# MCU_FM.net
KiCad netlist of a schematic drawn in Altium Designer
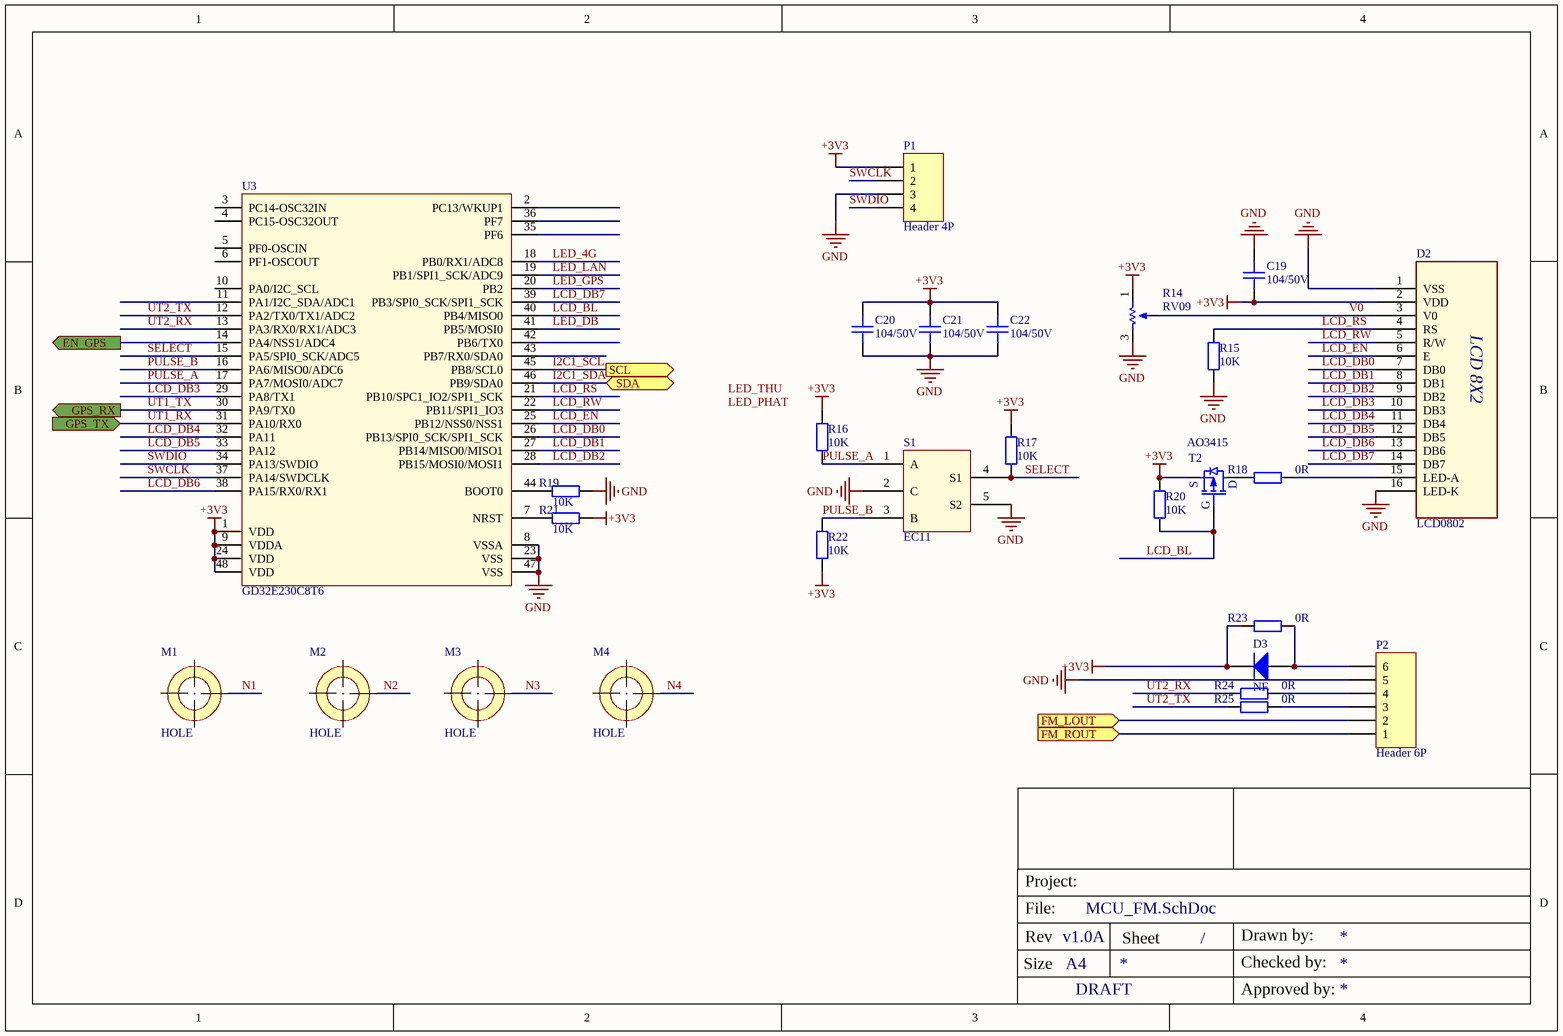
[diagram p0: MCU_FM.SchDoc]

(export (version "E")
  (design (tool "Eeschema 10.0.6"))
  (components
    (comp (ref "C19")
      (value "104/50V")
      (footprint "CAPC-0603 (1608) - HD")
      (description "CAP CER 0.1uF 50V 10% X7R 0603")
      (fields (field (name "MPN") "C0603C104K5RACTU"))
      (libsource (lib "01.Passives") (part "C0603C104K5RACTU"))
    )
    (comp (ref "C20")
      (value "104/50V")
      (footprint "CAPC-0603 (1608) - HD")
      (description "CAP CER 0.1uF 50V 10% X7R 0603")
      (fields (field (name "MPN") "C0603C104K5RACTU"))
      (libsource (lib "01.Passives") (part "C0603C104K5RACTU"))
    )
    (comp (ref "C21")
      (value "104/50V")
      (footprint "CAPC-0603 (1608) - HD")
      (description "CAP CER 0.1uF 50V 10% X7R 0603")
      (fields (field (name "MPN") "C0603C104K5RACTU"))
      (libsource (lib "01.Passives") (part "C0603C104K5RACTU"))
    )
    (comp (ref "C22")
      (value "104/50V")
      (footprint "CAPC-0603 (1608) - HD")
      (description "CAP CER 0.1uF 50V 10% X7R 0603")
      (fields (field (name "MPN") "C0603C104K5RACTU"))
      (libsource (lib "01.Passives") (part "C0603C104K5RACTU"))
    )
    (comp (ref "D2")
      (value "LCD0802")
      (footprint "LCD 8X2 FORM 3")
      (fields (field (name "MFR") "China"))
      (libsource (lib "08.Miscellaneous") (part "LCD0802"))
    )
    (comp (ref "D3")
      (value "NF")
      (footprint "SOD-123")
      (description "Diode Standard 100V 300mA (DC) Surface Mount SOD-123")
      (fields (field (name "PART NUMBER") "1N4148W-7-F"))
      (libsource (lib "Library_Chip") (part "Diode 1N4148"))
    )
    (comp (ref "M1")
      (value "HOLE")
      (footprint "HOLE_3MM_6MM")
      (description "3mm/5mm")
      (fields (field (name "MPN") "None"))
      (libsource (lib "08.Miscellaneous") (part "HOLE_3_5"))
    )
    (comp (ref "M2")
      (value "HOLE")
      (footprint "HOLE_3MM_6MM")
      (description "3mm/5mm")
      (fields (field (name "MPN") "None"))
      (libsource (lib "08.Miscellaneous") (part "HOLE_3_5"))
    )
    (comp (ref "M3")
      (value "HOLE")
      (footprint "HOLE_3MM_6MM")
      (description "3mm/5mm")
      (fields (field (name "MPN") "None"))
      (libsource (lib "08.Miscellaneous") (part "HOLE_3_5"))
    )
    (comp (ref "M4")
      (value "HOLE")
      (footprint "HOLE_3MM_6MM")
      (description "3mm/5mm")
      (fields (field (name "MPN") "None"))
      (libsource (lib "08.Miscellaneous") (part "HOLE_3_5"))
    )
    (comp (ref "P1")
      (value "Header 4P")
      (footprint "HDR1X4 - W")
      (description "Header, 4 Pin Pitch 2.54mm")
      (fields (field (name "MPN") "S1012EC-40-ND"))
      (libsource (lib "04.Header-Connecter") (part "Header 4x1"))
    )
    (comp (ref "P2")
      (value "Header 6P")
      (footprint "HDR1X6 - W")
      (description "Header, 6 Pin Pitch 2.54mm")
      (fields (field (name "MPN") "S1012EC-40-ND"))
      (libsource (lib "04.Header-Connecter") (part "Header 6x1"))
    )
    (comp (ref "R14")
      (value "RV09")
      (footprint "RES_VAR_Type1")
      (description "Variable Resistor 10K")
      (libsource (lib "01.Passives") (part "Res Var RV09"))
    )
    (comp (ref "R15")
      (value "10K")
      (footprint "RESC-0603 (1608) - HD")
      (description "RES SMD 10K OHM 1% 1/10W 0603")
      (fields (field (name "MPN") "RC0603FR-0710KL"))
      (libsource (lib "01.Passives") (part "RC0603FR-0710KL"))
    )
    (comp (ref "R16")
      (value "10K")
      (footprint "RESC-0603 (1608) - HD")
      (description "RES SMD 10K OHM 1% 1/10W 0603")
      (fields (field (name "MPN") "RC0603FR-0710KL"))
      (libsource (lib "01.Passives") (part "RC0603FR-0710KL"))
    )
    (comp (ref "R17")
      (value "10K")
      (footprint "RESC-0603 (1608) - HD")
      (description "RES SMD 10K OHM 1% 1/10W 0603")
      (fields (field (name "MPN") "RC0603FR-0710KL"))
      (libsource (lib "01.Passives") (part "RC0603FR-0710KL"))
    )
    (comp (ref "R18")
      (value "0R")
      (footprint "RESC-0603 (1608) - HD")
      (description "RES SMD 0.0OHM JUMPER 1/10W 0603")
      (fields (field (name "MPN") "RC0603FR-070RL"))
      (libsource (lib "01.Passives") (part "RC0603FR-070RL"))
    )
    (comp (ref "R19")
      (value "10K")
      (footprint "RESC-0603 (1608) - HD")
      (description "RES SMD 10K OHM 1% 1/10W 0603")
      (fields (field (name "MPN") "RC0603FR-0710KL"))
      (libsource (lib "") (part "RC0603FR-0710KL_1"))
    )
    (comp (ref "R20")
      (value "10K")
      (footprint "RESC-0603 (1608) - HD")
      (description "RES SMD 10K OHM 1% 1/10W 0603")
      (fields (field (name "MPN") "RC0603FR-0710KL"))
      (libsource (lib "01.Passives") (part "RC0603FR-0710KL"))
    )
    (comp (ref "R21")
      (value "10K")
      (footprint "RESC-0603 (1608) - HD")
      (description "RES SMD 10K OHM 1% 1/10W 0603")
      (fields (field (name "MPN") "RC0603FR-0710KL"))
      (libsource (lib "") (part "RC0603FR-0710KL_1"))
    )
    (comp (ref "R22")
      (value "10K")
      (footprint "RESC-0603 (1608) - HD")
      (description "RES SMD 10K OHM 1% 1/10W 0603")
      (fields (field (name "MPN") "RC0603FR-0710KL"))
      (libsource (lib "") (part "RC0603FR-0710KL_2"))
    )
    (comp (ref "R23")
      (value "0R")
      (footprint "RESC-0603 (1608) - HD")
      (description "RES SMD 0.0OHM JUMPER 1/10W 0603")
      (fields (field (name "MPN") "RC0603FR-070RL"))
      (libsource (lib "01.Passives") (part "RC0603FR-070RL"))
    )
    (comp (ref "R24")
      (value "0R")
      (footprint "RESC-0603 (1608) - HD")
      (description "RES SMD 0.0OHM JUMPER 1/10W 0603")
      (fields (field (name "MPN") "RC0603FR-070RL"))
      (libsource (lib "01.Passives") (part "RC0603FR-070RL"))
    )
    (comp (ref "R25")
      (value "0R")
      (footprint "RESC-0603 (1608) - HD")
      (description "RES SMD 0.0OHM JUMPER 1/10W 0603")
      (fields (field (name "MPN") "RC0603FR-070RL"))
      (libsource (lib "01.Passives") (part "RC0603FR-070RL"))
    )
    (comp (ref "S1")
      (value "EC11")
      (footprint "EC11")
      (description "ENCODER SW EC11 - 20mm")
      (fields (field (name "MFR") "China"))
      (libsource (lib "08.Miscellaneous") (part "EC11"))
    )
    (comp (ref "T2")
      (value "AO3415")
      (footprint "SOT23_3")
      (description "MOSFET P-CH 20V 4A SOT23")
      (fields (field (name "MFR") "Alpha & Omega Semiconductor Inc."))
      (libsource (lib "03.Semiconductor") (part "AO3415"))
    )
    (comp (ref "U3")
      (value "GD32E230C8T6")
      (footprint "LQFP-48")
      (description "ARM® Cortex®-M23 32-bit MCU 64K Flash 8K RAM")
      (fields (field (name "MFR") "Gigadevice"))
      (libsource (lib "05.IC") (part "GD32E230C8T6"))
    )
  )
  (nets
    (net (code "1") (name "+3V3") (class "Default")
      (node (ref "C19") (pin "2") (pinfunction "2_2") (pintype "passive"))
      (node (ref "C20") (pin "2") (pinfunction "2_2") (pintype "passive"))
      (node (ref "C21") (pin "2") (pinfunction "2_2") (pintype "passive"))
      (node (ref "C22") (pin "2") (pinfunction "2_2") (pintype "passive"))
      (node (ref "D2") (pin "2") (pinfunction "VDD_2") (pintype "passive"))
      (node (ref "D3") (pin "2") (pinfunction "K_2") (pintype "passive"))
      (node (ref "P1") (pin "1") (pinfunction "1_1") (pintype "passive"))
      (node (ref "R14") (pin "1") (pinfunction "1_1") (pintype "passive"))
      (node (ref "R16") (pin "2") (pinfunction "2_2") (pintype "passive"))
      (node (ref "R17") (pin "2") (pinfunction "2_2") (pintype "passive"))
      (node (ref "R20") (pin "2") (pinfunction "2_2") (pintype "passive"))
      (node (ref "R21") (pin "2") (pinfunction "2_2") (pintype "passive"))
      (node (ref "R22") (pin "2") (pinfunction "2_2") (pintype "passive"))
      (node (ref "R23") (pin "1") (pinfunction "1_1") (pintype "passive"))
      (node (ref "T2") (pin "2") (pinfunction "S_2") (pintype "passive"))
      (node (ref "U3") (pin "1") (pinfunction "VDD_1") (pintype "power_in"))
      (node (ref "U3") (pin "24") (pinfunction "VDD_24") (pintype "power_in"))
      (node (ref "U3") (pin "48") (pinfunction "VDD_48") (pintype "power_in"))
      (node (ref "U3") (pin "9") (pinfunction "VDDA_9") (pintype "power_in"))
    )
    (net (code "2") (name "/EN_GPS") (class "Default")
      (node (ref "U3") (pin "14") (pinfunction "PA4/NSS1/ADC4_14") (pintype "power_in"))
    )
    (net (code "3") (name "/FM_LOUT") (class "Default")
      (node (ref "P2") (pin "2") (pinfunction "2_2") (pintype "passive"))
    )
    (net (code "4") (name "/FM_ROUT") (class "Default")
      (node (ref "P2") (pin "1") (pinfunction "1_1") (pintype "passive"))
    )
    (net (code "5") (name "/I2C1_SCL") (class "Default")
      (node (ref "U3") (pin "45") (pinfunction "PB8/SCL0_45") (pintype "passive"))
    )
    (net (code "6") (name "/I2C1_SDA") (class "Default")
      (node (ref "U3") (pin "46") (pinfunction "PB9/SDA0_46") (pintype "passive"))
    )
    (net (code "7") (name "/LCD_BL") (class "Default")
      (node (ref "R20") (pin "1") (pinfunction "1_1") (pintype "passive"))
      (node (ref "T2") (pin "1") (pinfunction "G_1") (pintype "passive"))
      (node (ref "U3") (pin "40") (pinfunction "PB4/MISO0_40") (pintype "power_in"))
    )
    (net (code "8") (name "/LCD_DB0") (class "Default")
      (node (ref "D2") (pin "7") (pinfunction "DB0_7") (pintype "passive"))
      (node (ref "U3") (pin "26") (pinfunction "PB13/SPI0_SCK/SPI1_SCK_26") (pintype "power_in"))
    )
    (net (code "9") (name "/LCD_DB1") (class "Default")
      (node (ref "D2") (pin "8") (pinfunction "DB1_8") (pintype "passive"))
      (node (ref "U3") (pin "27") (pinfunction "PB14/MISO0/MISO1_27") (pintype "power_in"))
    )
    (net (code "10") (name "/LCD_DB2") (class "Default")
      (node (ref "D2") (pin "9") (pinfunction "DB2_9") (pintype "passive"))
      (node (ref "U3") (pin "28") (pinfunction "PB15/MOSI0/MOSI1_28") (pintype "power_in"))
    )
    (net (code "11") (name "/LCD_DB3") (class "Default")
      (node (ref "D2") (pin "10") (pinfunction "DB3_10") (pintype "passive"))
      (node (ref "U3") (pin "29") (pinfunction "PA8/TX1_29") (pintype "power_in"))
    )
    (net (code "12") (name "/LCD_DB4") (class "Default")
      (node (ref "D2") (pin "11") (pinfunction "DB4_11") (pintype "passive"))
      (node (ref "U3") (pin "32") (pinfunction "PA11_32") (pintype "power_in"))
    )
    (net (code "13") (name "/LCD_DB5") (class "Default")
      (node (ref "D2") (pin "12") (pinfunction "DB5_12") (pintype "passive"))
      (node (ref "U3") (pin "33") (pinfunction "PA12_33") (pintype "power_in"))
    )
    (net (code "14") (name "/LCD_DB6") (class "Default")
      (node (ref "D2") (pin "13") (pinfunction "DB6_13") (pintype "passive"))
      (node (ref "U3") (pin "38") (pinfunction "PA15/RX0/RX1_38") (pintype "power_in"))
    )
    (net (code "15") (name "/LCD_DB7") (class "Default")
      (node (ref "D2") (pin "14") (pinfunction "DB7_14") (pintype "passive"))
      (node (ref "U3") (pin "39") (pinfunction "PB3/SPI0_SCK/SPI1_SCK_39") (pintype "power_in"))
    )
    (net (code "16") (name "/LCD_EN") (class "Default")
      (node (ref "D2") (pin "6") (pinfunction "E_6") (pintype "passive"))
      (node (ref "U3") (pin "25") (pinfunction "PB12/NSS0/NSS1_25") (pintype "power_in"))
    )
    (net (code "17") (name "/LCD_RS") (class "Default")
      (node (ref "D2") (pin "4") (pinfunction "RS_4") (pintype "passive"))
      (node (ref "R15") (pin "2") (pinfunction "2_2") (pintype "passive"))
      (node (ref "U3") (pin "21") (pinfunction "PB10/SPC1_IO2/SPI1_SCK_21") (pintype "power_in"))
    )
    (net (code "18") (name "/LCD_RW") (class "Default")
      (node (ref "D2") (pin "5") (pinfunction "R/W_5") (pintype "passive"))
      (node (ref "U3") (pin "22") (pinfunction "PB11/SPI1_IO3_22") (pintype "power_in"))
    )
    (net (code "19") (name "/LED_4G") (class "Default")
      (node (ref "U3") (pin "18") (pinfunction "PB0/RX1/ADC8_18") (pintype "power_in"))
    )
    (net (code "20") (name "/LED_DB") (class "Default")
      (node (ref "U3") (pin "41") (pinfunction "PB5/MOSI0_41") (pintype "power_in"))
    )
    (net (code "21") (name "/LED_GPS") (class "Default")
      (node (ref "U3") (pin "20") (pinfunction "PB2_20") (pintype "power_in"))
    )
    (net (code "22") (name "/LED_LAN") (class "Default")
      (node (ref "U3") (pin "19") (pinfunction "PB1/SPI1_SCK/ADC9_19") (pintype "power_in"))
    )
    (net (code "29") (name "/PULSE_A") (class "Default")
      (node (ref "R16") (pin "1") (pinfunction "1_1") (pintype "passive"))
      (node (ref "S1") (pin "1") (pinfunction "A_1") (pintype "passive"))
      (node (ref "U3") (pin "17") (pinfunction "PA7/MOSI0/ADC7_17") (pintype "power_in"))
    )
    (net (code "30") (name "/PULSE_B") (class "Default")
      (node (ref "R22") (pin "1") (pinfunction "1_1") (pintype "passive"))
      (node (ref "S1") (pin "3") (pinfunction "B_3") (pintype "passive"))
      (node (ref "U3") (pin "16") (pinfunction "PA6/MISO0/ADC6_16") (pintype "power_in"))
    )
    (net (code "31") (name "/SELECT") (class "Default")
      (node (ref "R17") (pin "1") (pinfunction "1_1") (pintype "passive"))
      (node (ref "S1") (pin "4") (pinfunction "S1_4") (pintype "passive"))
      (node (ref "U3") (pin "15") (pinfunction "PA5/SPI0_SCK/ADC5_15") (pintype "power_in"))
    )
    (net (code "32") (name "/SWCLK") (class "Default")
      (node (ref "P1") (pin "2") (pinfunction "2_2") (pintype "passive"))
      (node (ref "U3") (pin "37") (pinfunction "PA14/SWDCLK_37") (pintype "power_in"))
    )
    (net (code "33") (name "/SWDIO") (class "Default")
      (node (ref "P1") (pin "4") (pinfunction "4_4") (pintype "passive"))
      (node (ref "U3") (pin "34") (pinfunction "PA13/SWDIO_34") (pintype "power_in"))
    )
    (net (code "34") (name "/UT1_RX") (class "Default")
      (node (ref "U3") (pin "31") (pinfunction "PA10/RX0_31") (pintype "passive"))
    )
    (net (code "35") (name "/UT1_TX") (class "Default")
      (node (ref "U3") (pin "30") (pinfunction "PA9/TX0_30") (pintype "passive"))
    )
    (net (code "36") (name "/UT2_RX") (class "Default")
      (node (ref "R24") (pin "1") (pinfunction "1_1") (pintype "passive"))
      (node (ref "U3") (pin "13") (pinfunction "PA3/RX0/RX1/ADC3_13") (pintype "power_in"))
    )
    (net (code "37") (name "/UT2_TX") (class "Default")
      (node (ref "R25") (pin "1") (pinfunction "1_1") (pintype "passive"))
      (node (ref "U3") (pin "12") (pinfunction "PA2/TX0/TX1/ADC2_12") (pintype "power_in"))
    )
    (net (code "38") (name "/V0") (class "Default")
      (node (ref "D2") (pin "3") (pinfunction "V0_3") (pintype "passive"))
      (node (ref "R14") (pin "2") (pinfunction "2_2") (pintype "passive"))
    )
    (net (code "39") (name "GND") (class "Default")
      (node (ref "C19") (pin "1") (pinfunction "1_1") (pintype "passive"))
      (node (ref "C20") (pin "1") (pinfunction "1_1") (pintype "passive"))
      (node (ref "C21") (pin "1") (pinfunction "1_1") (pintype "passive"))
      (node (ref "C22") (pin "1") (pinfunction "1_1") (pintype "passive"))
      (node (ref "D2") (pin "1") (pinfunction "VSS_1") (pintype "passive"))
      (node (ref "D2") (pin "16") (pinfunction "LED-K_16") (pintype "passive"))
      (node (ref "P1") (pin "3") (pinfunction "3_3") (pintype "passive"))
      (node (ref "P2") (pin "5") (pinfunction "5_5") (pintype "passive"))
      (node (ref "R14") (pin "3") (pinfunction "3_3") (pintype "passive"))
      (node (ref "R15") (pin "1") (pinfunction "1_1") (pintype "passive"))
      (node (ref "R19") (pin "2") (pinfunction "2_2") (pintype "passive"))
      (node (ref "S1") (pin "2") (pinfunction "C_2") (pintype "passive"))
      (node (ref "S1") (pin "5") (pinfunction "S2_5") (pintype "passive"))
      (node (ref "U3") (pin "23") (pinfunction "VSS_23") (pintype "power_in"))
      (node (ref "U3") (pin "47") (pinfunction "VSS_47") (pintype "power_in"))
      (node (ref "U3") (pin "8") (pinfunction "VSSA_8") (pintype "power_in"))
    )
    (net (code "40") (name "Net-(D2-LED-A)") (class "Default")
      (node (ref "D2") (pin "15") (pinfunction "LED-A_15") (pintype "passive"))
      (node (ref "R18") (pin "2") (pinfunction "2_2") (pintype "passive"))
    )
    (net (code "41") (name "Net-(D3-A)") (class "Default")
      (node (ref "D3") (pin "1") (pinfunction "A_1") (pintype "passive"))
      (node (ref "P2") (pin "6") (pinfunction "6_6") (pintype "passive"))
      (node (ref "R23") (pin "2") (pinfunction "2_2") (pintype "passive"))
    )
    (net (code "42") (name "Net-(P2-Pad3)") (class "Default")
      (node (ref "P2") (pin "3") (pinfunction "3_3") (pintype "passive"))
      (node (ref "R25") (pin "2") (pinfunction "2_2") (pintype "passive"))
    )
    (net (code "43") (name "Net-(P2-Pad4)") (class "Default")
      (node (ref "P2") (pin "4") (pinfunction "4_4") (pintype "passive"))
      (node (ref "R24") (pin "2") (pinfunction "2_2") (pintype "passive"))
    )
    (net (code "44") (name "Net-(T2-D)") (class "Default")
      (node (ref "R18") (pin "1") (pinfunction "1_1") (pintype "passive"))
      (node (ref "T2") (pin "3") (pinfunction "D_3") (pintype "passive"))
    )
    (net (code "45") (name "Net-(U3-BOOT0)") (class "Default")
      (node (ref "R19") (pin "1") (pinfunction "1_1") (pintype "passive"))
      (node (ref "U3") (pin "44") (pinfunction "BOOT0_44") (pintype "power_in"))
    )
    (net (code "46") (name "Net-(U3-NRST)") (class "Default")
      (node (ref "R21") (pin "1") (pinfunction "1_1") (pintype "passive"))
      (node (ref "U3") (pin "7") (pinfunction "NRST_7") (pintype "power_in"))
    )
    (net (code "47") (name "unconnected-(U3-PA0{slash}I2C_SCL-Pad10)") (class "Default")
      (node (ref "U3") (pin "10") (pinfunction "PA0/I2C_SCL_10") (pintype "power_in"))
    )
    (net (code "48") (name "unconnected-(U3-PA1{slash}I2C_SDA{slash}ADC1-Pad11)") (class "Default")
      (node (ref "U3") (pin "11") (pinfunction "PA1/I2C_SDA/ADC1_11") (pintype "power_in"))
    )
    (net (code "49") (name "unconnected-(U3-PB6{slash}TX0-Pad42)") (class "Default")
      (node (ref "U3") (pin "42") (pinfunction "PB6/TX0_42") (pintype "power_in"))
    )
    (net (code "50") (name "unconnected-(U3-PB7{slash}RX0{slash}SDA0-Pad43)") (class "Default")
      (node (ref "U3") (pin "43") (pinfunction "PB7/RX0/SDA0_43") (pintype "passive"))
    )
    (net (code "51") (name "unconnected-(U3-PC13{slash}WKUP1-Pad2)") (class "Default")
      (node (ref "U3") (pin "2") (pinfunction "PC13/WKUP1_2") (pintype "passive"))
    )
    (net (code "52") (name "unconnected-(U3-PC14-OSC32IN-Pad3)") (class "Default")
      (node (ref "U3") (pin "3") (pinfunction "PC14-OSC32IN_3") (pintype "power_in"))
    )
    (net (code "53") (name "unconnected-(U3-PC15-OSC32OUT-Pad4)") (class "Default")
      (node (ref "U3") (pin "4") (pinfunction "PC15-OSC32OUT_4") (pintype "power_in"))
    )
    (net (code "54") (name "unconnected-(U3-PF0-OSCIN-Pad5)") (class "Default")
      (node (ref "U3") (pin "5") (pinfunction "PF0-OSCIN_5") (pintype "power_in"))
    )
    (net (code "55") (name "unconnected-(U3-PF1-OSCOUT-Pad6)") (class "Default")
      (node (ref "U3") (pin "6") (pinfunction "PF1-OSCOUT_6") (pintype "power_in"))
    )
    (net (code "56") (name "unconnected-(U3-PF6-Pad35)") (class "Default")
      (node (ref "U3") (pin "35") (pinfunction "PF6_35") (pintype "power_in"))
    )
    (net (code "57") (name "unconnected-(U3-PF7-Pad36)") (class "Default")
      (node (ref "U3") (pin "36") (pinfunction "PF7_36") (pintype "power_in"))
    )
  )
)
